# AlertTickets.net
KiCad netlist of a schematic drawn in EAGLE
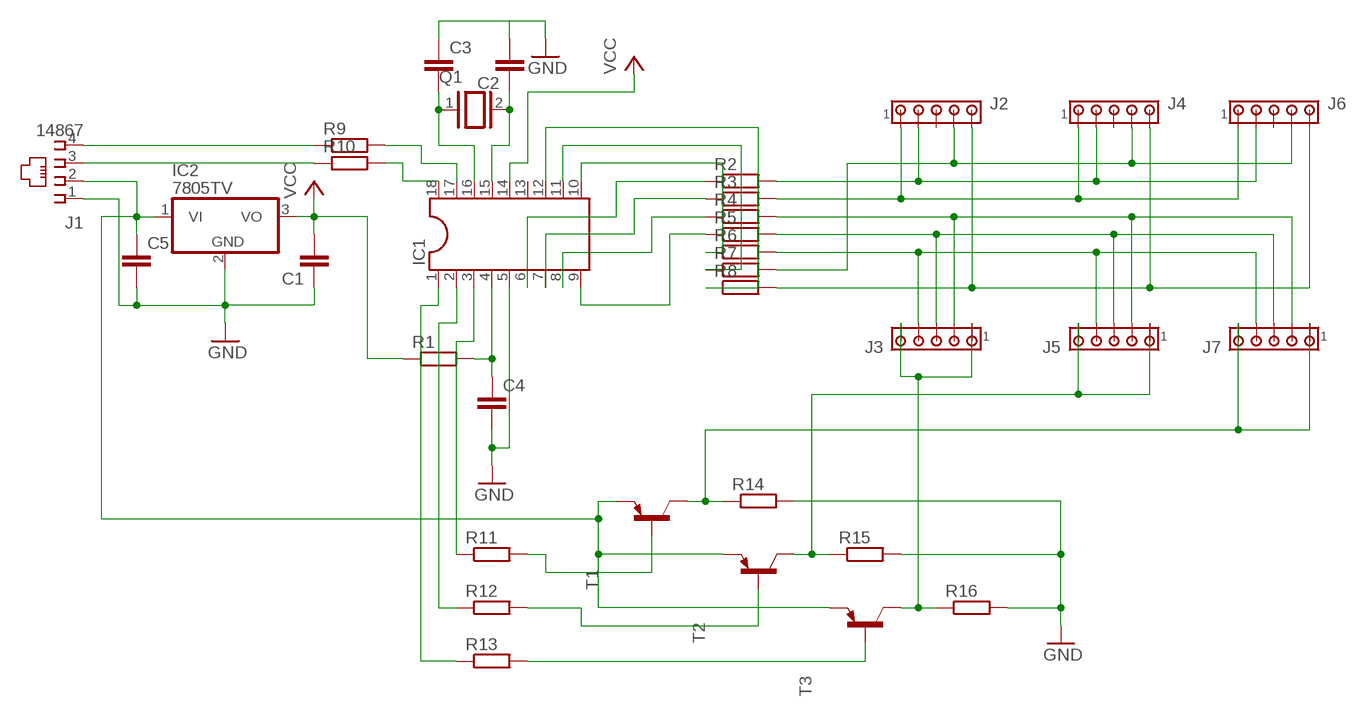
[diagram p0: schematic, sheet 1]

(export (version "E")
  (design (tool "Eeschema 10.0.6"))
  (components
    (comp (ref "C1")
      (value "C-EU050-024X044")
      (footprint "eagle-import:C050-024X044")
      (libsource (lib "eagle-import") (part "C-EU050-024X044"))
    )
    (comp (ref "C2")
      (value "C-EU050-024X044")
      (footprint "eagle-import:C050-024X044")
      (libsource (lib "eagle-import") (part "C-EU050-024X044"))
    )
    (comp (ref "C3")
      (value "C-EU050-024X044")
      (footprint "eagle-import:C050-024X044")
      (libsource (lib "eagle-import") (part "C-EU050-024X044"))
    )
    (comp (ref "C4")
      (value "C-EU050-024X044")
      (footprint "eagle-import:C050-024X044")
      (libsource (lib "eagle-import") (part "C-EU050-024X044"))
    )
    (comp (ref "C5")
      (value "C-EU050-024X044")
      (footprint "eagle-import:C050-024X044")
      (libsource (lib "eagle-import") (part "C-EU050-024X044"))
    )
    (comp (ref "IC1")
      (value "DIL18")
      (footprint "eagle-import:DIL18")
      (libsource (lib "eagle-import") (part "DIL18"))
    )
    (comp (ref "IC2")
      (value "7805TV")
      (footprint "eagle-import:TO220V")
      (libsource (lib "eagle-import") (part "78TV05"))
    )
    (comp (ref "J1")
      (value "14867")
      (footprint "eagle-import:14867")
      (libsource (lib "eagle-import") (part "14867"))
    )
    (comp (ref "J2")
      (value "MTA05-100")
      (footprint "eagle-import:10X05MTA")
      (libsource (lib "eagle-import") (part "MTA05-100"))
    )
    (comp (ref "J3")
      (value "MTA05-100")
      (footprint "eagle-import:10X05MTA")
      (libsource (lib "eagle-import") (part "MTA05-100"))
    )
    (comp (ref "J4")
      (value "MTA05-100")
      (footprint "eagle-import:10X05MTA")
      (libsource (lib "eagle-import") (part "MTA05-100"))
    )
    (comp (ref "J5")
      (value "MTA05-100")
      (footprint "eagle-import:10X05MTA")
      (libsource (lib "eagle-import") (part "MTA05-100"))
    )
    (comp (ref "J6")
      (value "MTA05-100")
      (footprint "eagle-import:10X05MTA")
      (libsource (lib "eagle-import") (part "MTA05-100"))
    )
    (comp (ref "J7")
      (value "MTA05-100")
      (footprint "eagle-import:10X05MTA")
      (libsource (lib "eagle-import") (part "MTA05-100"))
    )
    (comp (ref "Q1")
      (value "XTAL/S")
      (footprint "eagle-import:QS")
      (libsource (lib "eagle-import") (part "XTAL/S"))
    )
    (comp (ref "R1")
      (value "R-EU_0207/12")
      (footprint "eagle-import:0207_12")
      (libsource (lib "eagle-import") (part "R-EU_0207/12"))
    )
    (comp (ref "R2")
      (value "R-EU_0207/12")
      (footprint "eagle-import:0207_12")
      (libsource (lib "eagle-import") (part "R-EU_0207/12"))
    )
    (comp (ref "R3")
      (value "R-EU_0207/12")
      (footprint "eagle-import:0207_12")
      (libsource (lib "eagle-import") (part "R-EU_0207/12"))
    )
    (comp (ref "R4")
      (value "R-EU_0207/12")
      (footprint "eagle-import:0207_12")
      (libsource (lib "eagle-import") (part "R-EU_0207/12"))
    )
    (comp (ref "R5")
      (value "R-EU_0207/12")
      (footprint "eagle-import:0207_12")
      (libsource (lib "eagle-import") (part "R-EU_0207/12"))
    )
    (comp (ref "R6")
      (value "R-EU_0207/12")
      (footprint "eagle-import:0207_12")
      (libsource (lib "eagle-import") (part "R-EU_0207/12"))
    )
    (comp (ref "R7")
      (value "R-EU_0207/12")
      (footprint "eagle-import:0207_12")
      (libsource (lib "eagle-import") (part "R-EU_0207/12"))
    )
    (comp (ref "R8")
      (value "R-EU_0207/12")
      (footprint "eagle-import:0207_12")
      (libsource (lib "eagle-import") (part "R-EU_0207/12"))
    )
    (comp (ref "R9")
      (value "R-EU_0207/12")
      (footprint "eagle-import:0207_12")
      (libsource (lib "eagle-import") (part "R-EU_0207/12"))
    )
    (comp (ref "R10")
      (value "R-EU_0207/12")
      (footprint "eagle-import:0207_12")
      (libsource (lib "eagle-import") (part "R-EU_0207/12"))
    )
    (comp (ref "R11")
      (value "R-EU_0207/12")
      (footprint "eagle-import:0207_12")
      (libsource (lib "eagle-import") (part "R-EU_0207/12"))
    )
    (comp (ref "R12")
      (value "R-EU_0207/12")
      (footprint "eagle-import:0207_12")
      (libsource (lib "eagle-import") (part "R-EU_0207/12"))
    )
    (comp (ref "R13")
      (value "R-EU_0207/12")
      (footprint "eagle-import:0207_12")
      (libsource (lib "eagle-import") (part "R-EU_0207/12"))
    )
    (comp (ref "R14")
      (value "R-EU_0207/12")
      (footprint "eagle-import:0207_12")
      (libsource (lib "eagle-import") (part "R-EU_0207/12"))
    )
    (comp (ref "R15")
      (value "R-EU_0207/12")
      (footprint "eagle-import:0207_12")
      (libsource (lib "eagle-import") (part "R-EU_0207/12"))
    )
    (comp (ref "R16")
      (value "R-EU_0207/12")
      (footprint "eagle-import:0207_12")
      (libsource (lib "eagle-import") (part "R-EU_0207/12"))
    )
    (comp (ref "T1")
      (value "2N3906-PNP-TO92-EBC")
      (footprint "eagle-import:TO92-EBC")
      (libsource (lib "eagle-import") (part "-PNP-TO92-EBC2N3906"))
    )
    (comp (ref "T2")
      (value "2N3906-PNP-TO92-EBC")
      (footprint "eagle-import:TO92-EBC")
      (libsource (lib "eagle-import") (part "-PNP-TO92-EBC2N3906"))
    )
    (comp (ref "T3")
      (value "2N3906-PNP-TO92-EBC")
      (footprint "eagle-import:TO92-EBC")
      (libsource (lib "eagle-import") (part "-PNP-TO92-EBC2N3906"))
    )
  )
  (nets
    (net (code "1") (name "GND") (class "Default")
      (node (ref "C1") (pin "1") (pinfunction "1_1") (pintype "passive"))
      (node (ref "C2") (pin "2") (pinfunction "2_2") (pintype "passive"))
      (node (ref "C3") (pin "1") (pinfunction "1_1") (pintype "passive"))
      (node (ref "C4") (pin "2") (pinfunction "2_2") (pintype "passive"))
      (node (ref "C5") (pin "2") (pinfunction "2_2") (pintype "passive"))
      (node (ref "IC1") (pin "5") (pinfunction "5_5") (pintype "passive"))
      (node (ref "IC2") (pin "2") (pinfunction "GND_2") (pintype "passive"))
      (node (ref "J1") (pin "1") (pinfunction "1_1") (pintype "passive"))
      (node (ref "R14") (pin "2") (pinfunction "2_2") (pintype "passive"))
      (node (ref "R15") (pin "2") (pinfunction "2_2") (pintype "passive"))
      (node (ref "R16") (pin "2") (pinfunction "2_2") (pintype "passive"))
    )
    (net (code "2") (name "Net-(C2-Pad1)") (class "Default")
      (node (ref "C2") (pin "1") (pinfunction "1_1") (pintype "passive"))
      (node (ref "IC1") (pin "15") (pinfunction "15_15") (pintype "passive"))
      (node (ref "Q1") (pin "2") (pinfunction "2_2") (pintype "passive"))
    )
    (net (code "3") (name "Net-(C3-Pad2)") (class "Default")
      (node (ref "C3") (pin "2") (pinfunction "2_2") (pintype "passive"))
      (node (ref "IC1") (pin "16") (pinfunction "16_16") (pintype "passive"))
      (node (ref "Q1") (pin "1") (pinfunction "1_1") (pintype "passive"))
    )
    (net (code "4") (name "Net-(C4-Pad1)") (class "Default")
      (node (ref "C4") (pin "1") (pinfunction "1_1") (pintype "passive"))
      (node (ref "IC1") (pin "4") (pinfunction "4_4") (pintype "passive"))
      (node (ref "R1") (pin "2") (pinfunction "2_2") (pintype "passive"))
    )
    (net (code "5") (name "Net-(IC1-Pad1)") (class "Default")
      (node (ref "IC1") (pin "1") (pinfunction "1_1") (pintype "passive"))
      (node (ref "R13") (pin "1") (pinfunction "1_1") (pintype "passive"))
    )
    (net (code "6") (name "Net-(IC1-Pad2)") (class "Default")
      (node (ref "IC1") (pin "2") (pinfunction "2_2") (pintype "passive"))
      (node (ref "R12") (pin "1") (pinfunction "1_1") (pintype "passive"))
    )
    (net (code "7") (name "Net-(IC1-Pad3)") (class "Default")
      (node (ref "IC1") (pin "3") (pinfunction "3_3") (pintype "passive"))
      (node (ref "R11") (pin "1") (pinfunction "1_1") (pintype "passive"))
    )
    (net (code "8") (name "Net-(IC1-Pad6)") (class "Default")
      (node (ref "IC1") (pin "6") (pinfunction "6_6") (pintype "passive"))
      (node (ref "R2") (pin "1") (pinfunction "1_1") (pintype "passive"))
    )
    (net (code "9") (name "Net-(IC1-Pad7)") (class "Default")
      (node (ref "IC1") (pin "7") (pinfunction "7_7") (pintype "passive"))
      (node (ref "R3") (pin "1") (pinfunction "1_1") (pintype "passive"))
    )
    (net (code "10") (name "Net-(IC1-Pad8)") (class "Default")
      (node (ref "IC1") (pin "8") (pinfunction "8_8") (pintype "passive"))
      (node (ref "R4") (pin "1") (pinfunction "1_1") (pintype "passive"))
    )
    (net (code "11") (name "Net-(IC1-Pad9)") (class "Default")
      (node (ref "IC1") (pin "9") (pinfunction "9_9") (pintype "passive"))
      (node (ref "R5") (pin "1") (pinfunction "1_1") (pintype "passive"))
    )
    (net (code "12") (name "Net-(IC1-Pad10)") (class "Default")
      (node (ref "IC1") (pin "10") (pinfunction "10_10") (pintype "passive"))
      (node (ref "R6") (pin "1") (pinfunction "1_1") (pintype "passive"))
    )
    (net (code "13") (name "Net-(IC1-Pad11)") (class "Default")
      (node (ref "IC1") (pin "11") (pinfunction "11_11") (pintype "passive"))
      (node (ref "R7") (pin "1") (pinfunction "1_1") (pintype "passive"))
    )
    (net (code "14") (name "Net-(IC1-Pad12)") (class "Default")
      (node (ref "IC1") (pin "12") (pinfunction "12_12") (pintype "passive"))
      (node (ref "R8") (pin "1") (pinfunction "1_1") (pintype "passive"))
    )
    (net (code "15") (name "Net-(IC1-Pad17)") (class "Default")
      (node (ref "IC1") (pin "17") (pinfunction "17_17") (pintype "passive"))
      (node (ref "R9") (pin "2") (pinfunction "2_2") (pintype "passive"))
    )
    (net (code "16") (name "Net-(IC1-Pad18)") (class "Default")
      (node (ref "IC1") (pin "18") (pinfunction "18_18") (pintype "passive"))
      (node (ref "R10") (pin "2") (pinfunction "2_2") (pintype "passive"))
    )
    (net (code "17") (name "Net-(IC2-VI)") (class "Default")
      (node (ref "C5") (pin "1") (pinfunction "1_1") (pintype "passive"))
      (node (ref "IC2") (pin "1") (pinfunction "VI_1") (pintype "input"))
      (node (ref "J1") (pin "2") (pinfunction "2_2") (pintype "passive"))
      (node (ref "T1") (pin "E") (pinfunction "E_E") (pintype "passive"))
      (node (ref "T2") (pin "E") (pinfunction "E_E") (pintype "passive"))
      (node (ref "T3") (pin "E") (pinfunction "E_E") (pintype "passive"))
    )
    (net (code "18") (name "Net-(J1-Pad3)") (class "Default")
      (node (ref "J1") (pin "3") (pinfunction "3_3") (pintype "passive"))
      (node (ref "R10") (pin "1") (pinfunction "1_1") (pintype "passive"))
    )
    (net (code "19") (name "Net-(J1-Pad4)") (class "Default")
      (node (ref "J1") (pin "4") (pinfunction "4_4") (pintype "passive"))
      (node (ref "R9") (pin "1") (pinfunction "1_1") (pintype "passive"))
    )
    (net (code "20") (name "Net-(J2-Pad1)") (class "Default")
      (node (ref "J2") (pin "1") (pinfunction "1_1") (pintype "passive"))
      (node (ref "J4") (pin "1") (pinfunction "1_1") (pintype "passive"))
      (node (ref "J6") (pin "1") (pinfunction "1_1") (pintype "passive"))
      (node (ref "R3") (pin "2") (pinfunction "2_2") (pintype "passive"))
    )
    (net (code "21") (name "Net-(J2-Pad2)") (class "Default")
      (node (ref "J2") (pin "2") (pinfunction "2_2") (pintype "passive"))
      (node (ref "J4") (pin "2") (pinfunction "2_2") (pintype "passive"))
      (node (ref "J6") (pin "2") (pinfunction "2_2") (pintype "passive"))
      (node (ref "R2") (pin "2") (pinfunction "2_2") (pintype "passive"))
    )
    (net (code "22") (name "Net-(J2-Pad4)") (class "Default")
      (node (ref "J2") (pin "4") (pinfunction "4_4") (pintype "passive"))
      (node (ref "J4") (pin "4") (pinfunction "4_4") (pintype "passive"))
      (node (ref "J6") (pin "4") (pinfunction "4_4") (pintype "passive"))
      (node (ref "R7") (pin "2") (pinfunction "2_2") (pintype "passive"))
    )
    (net (code "23") (name "Net-(J2-Pad5)") (class "Default")
      (node (ref "J2") (pin "5") (pinfunction "5_5") (pintype "passive"))
      (node (ref "J4") (pin "5") (pinfunction "5_5") (pintype "passive"))
      (node (ref "J6") (pin "5") (pinfunction "5_5") (pintype "passive"))
      (node (ref "R8") (pin "2") (pinfunction "2_2") (pintype "passive"))
    )
    (net (code "24") (name "Net-(J3-Pad1)") (class "Default")
      (node (ref "J3") (pin "1") (pinfunction "1_1") (pintype "passive"))
      (node (ref "J3") (pin "5") (pinfunction "5_5") (pintype "passive"))
      (node (ref "R16") (pin "1") (pinfunction "1_1") (pintype "passive"))
      (node (ref "T3") (pin "C") (pinfunction "C_C") (pintype "passive"))
    )
    (net (code "25") (name "Net-(J3-Pad2)") (class "Default")
      (node (ref "J3") (pin "2") (pinfunction "2_2") (pintype "passive"))
      (node (ref "J5") (pin "2") (pinfunction "2_2") (pintype "passive"))
      (node (ref "J7") (pin "2") (pinfunction "2_2") (pintype "passive"))
      (node (ref "R4") (pin "2") (pinfunction "2_2") (pintype "passive"))
    )
    (net (code "26") (name "Net-(J3-Pad3)") (class "Default")
      (node (ref "J3") (pin "3") (pinfunction "3_3") (pintype "passive"))
      (node (ref "J5") (pin "3") (pinfunction "3_3") (pintype "passive"))
      (node (ref "J7") (pin "3") (pinfunction "3_3") (pintype "passive"))
      (node (ref "R5") (pin "2") (pinfunction "2_2") (pintype "passive"))
    )
    (net (code "27") (name "Net-(J3-Pad4)") (class "Default")
      (node (ref "J3") (pin "4") (pinfunction "4_4") (pintype "passive"))
      (node (ref "J5") (pin "4") (pinfunction "4_4") (pintype "passive"))
      (node (ref "J7") (pin "4") (pinfunction "4_4") (pintype "passive"))
      (node (ref "R6") (pin "2") (pinfunction "2_2") (pintype "passive"))
    )
    (net (code "28") (name "Net-(J5-Pad1)") (class "Default")
      (node (ref "J5") (pin "1") (pinfunction "1_1") (pintype "passive"))
      (node (ref "J5") (pin "5") (pinfunction "5_5") (pintype "passive"))
      (node (ref "R15") (pin "1") (pinfunction "1_1") (pintype "passive"))
      (node (ref "T2") (pin "C") (pinfunction "C_C") (pintype "passive"))
    )
    (net (code "29") (name "Net-(J7-Pad1)") (class "Default")
      (node (ref "J7") (pin "1") (pinfunction "1_1") (pintype "passive"))
      (node (ref "J7") (pin "5") (pinfunction "5_5") (pintype "passive"))
      (node (ref "R14") (pin "1") (pinfunction "1_1") (pintype "passive"))
      (node (ref "T1") (pin "C") (pinfunction "C_C") (pintype "passive"))
    )
    (net (code "30") (name "Net-(R11-Pad2)") (class "Default")
      (node (ref "R11") (pin "2") (pinfunction "2_2") (pintype "passive"))
      (node (ref "T1") (pin "B") (pinfunction "B_B") (pintype "passive"))
    )
    (net (code "31") (name "Net-(R12-Pad2)") (class "Default")
      (node (ref "R12") (pin "2") (pinfunction "2_2") (pintype "passive"))
      (node (ref "T2") (pin "B") (pinfunction "B_B") (pintype "passive"))
    )
    (net (code "32") (name "Net-(R13-Pad2)") (class "Default")
      (node (ref "R13") (pin "2") (pinfunction "2_2") (pintype "passive"))
      (node (ref "T3") (pin "B") (pinfunction "B_B") (pintype "passive"))
    )
    (net (code "33") (name "VCC") (class "Default")
      (node (ref "C1") (pin "2") (pinfunction "2_2") (pintype "passive"))
      (node (ref "IC1") (pin "14") (pinfunction "14_14") (pintype "passive"))
      (node (ref "IC2") (pin "3") (pinfunction "VO_3") (pintype "passive"))
      (node (ref "R1") (pin "1") (pinfunction "1_1") (pintype "passive"))
    )
    (net (code "34") (name "unconnected-(IC1-Pad13)") (class "Default")
      (node (ref "IC1") (pin "13") (pinfunction "13_13") (pintype "passive"))
    )
    (net (code "35") (name "unconnected-(J2-Pad3)") (class "Default")
      (node (ref "J2") (pin "3") (pinfunction "3_3") (pintype "passive"))
    )
    (net (code "36") (name "unconnected-(J4-Pad3)") (class "Default")
      (node (ref "J4") (pin "3") (pinfunction "3_3") (pintype "passive"))
    )
    (net (code "37") (name "unconnected-(J6-Pad3)") (class "Default")
      (node (ref "J6") (pin "3") (pinfunction "3_3") (pintype "passive"))
    )
  )
)
